# tof_board.net
KiCad netlist of a schematic drawn in Altium Designer
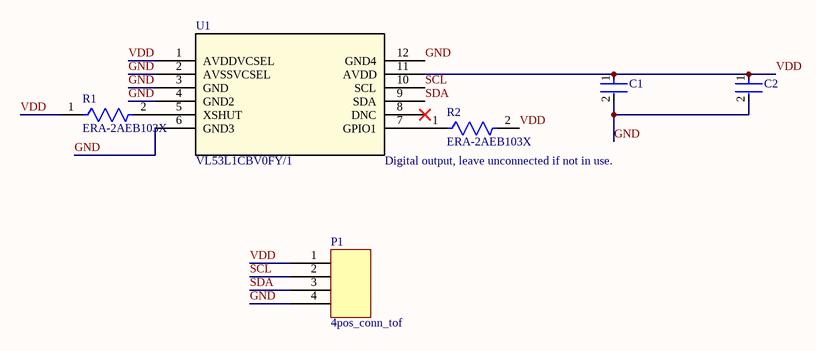
[diagram p0: tof_board.SchDoc]

(export (version "E")
  (design (tool "Eeschema 10.0.6"))
  (components
    (comp (ref "C1")
      (value "C0402C104K8PACTU")
      (footprint "FP-C0402-BB-MFG")
      (description "CAP CER 0.1UF 10V X5R 0402")
      (fields (field (name "MANUFACTURER") "Kemet") (field (name "TOLERANCE") "0.1"))
      (libsource (lib "Altium Content Vault") (part "b4654b650e69147ec39a6b967a45e02"))
    )
    (comp (ref "C2")
      (value "GRM155R60J475ME47D")
      (footprint "FP-GRM155-0_1-IPC_B")
      (description "Chip Multilayer Ceramic Capacitors for General Purpose, 0402, 4.7uF, X5R, 15%, 20%, 6.3V")
      (fields (field (name "VOLTAGE") "6.3V") (field (name "TOLERANCE") "20%"))
      (libsource (lib "Altium Content Vault") (part "11868f565c42a9108669ba33697ecf6"))
    )
    (comp (ref "P1")
      (value "4pos_conn_tof")
      (footprint "4pos_conn_tof")
      (libsource (lib "tof_board") (part "4pos_conn_tof"))
    )
    (comp (ref "R1")
      (value "ERA-2AEB103X")
      (footprint "FP-ERA2A-MFG")
      (description "RES SMD 10K OHM 0.1% 1/16W 0402")
      (fields (field (name "TOLERANCE") "0.1%") (field (name "MANUFACTURER") "Panasonic"))
      (libsource (lib "Altium Content Vault") (part "1029c3af85768c4190bb7ad29bc67b5"))
    )
    (comp (ref "R2")
      (value "ERA-2AEB103X")
      (footprint "FP-ERA2A-MFG")
      (description "RES SMD 10K OHM 0.1% 1/16W 0402")
      (fields (field (name "TOLERANCE") "0.1%") (field (name "MANUFACTURER") "Panasonic"))
      (libsource (lib "Altium Content Vault") (part "1029c3af85768c4190bb7ad29bc67b5"))
    )
    (comp (ref "U1")
      (value "VL53L1CBV0FY/1")
      (footprint "QFN_BV0FY/1_STM")
      (description "No Description Available")
      (fields (field (name "COPYRIGHT") "Copyright (C) 2022 Ultra Librarian. All rights reserved."))
      (libsource (lib "tof_board") (part "VL53L1CBV0FY/1"))
    )
  )
  (nets
    (net (code "1") (name "/GND") (class "Default")
      (node (ref "C1") (pin "2") (pinfunction "2_2") (pintype "passive"))
      (node (ref "C2") (pin "2") (pinfunction "2_2") (pintype "passive"))
      (node (ref "P1") (pin "4") (pinfunction "4_4") (pintype "passive"))
      (node (ref "U1") (pin "12") (pinfunction "GND4_12") (pintype "passive"))
      (node (ref "U1") (pin "2") (pinfunction "AVSSVCSEL_2") (pintype "passive"))
      (node (ref "U1") (pin "3") (pinfunction "GND_3") (pintype "passive"))
      (node (ref "U1") (pin "4") (pinfunction "GND2_4") (pintype "passive"))
      (node (ref "U1") (pin "6") (pinfunction "GND3_6") (pintype "passive"))
    )
    (net (code "2") (name "/SCL") (class "Default")
      (node (ref "P1") (pin "2") (pinfunction "2_2") (pintype "passive"))
      (node (ref "U1") (pin "10") (pinfunction "SCL_10") (pintype "passive"))
    )
    (net (code "3") (name "/SDA") (class "Default")
      (node (ref "P1") (pin "3") (pinfunction "3_3") (pintype "passive"))
      (node (ref "U1") (pin "9") (pinfunction "SDA_9") (pintype "passive"))
    )
    (net (code "4") (name "/VDD") (class "Default")
      (node (ref "C1") (pin "1") (pinfunction "1_1") (pintype "passive"))
      (node (ref "C2") (pin "1") (pinfunction "1_1") (pintype "passive"))
      (node (ref "P1") (pin "1") (pinfunction "1_1") (pintype "passive"))
      (node (ref "R1") (pin "1") (pinfunction "1_1") (pintype "passive"))
      (node (ref "R2") (pin "2") (pinfunction "2_2") (pintype "passive"))
      (node (ref "U1") (pin "1") (pinfunction "AVDDVCSEL_1") (pintype "power_in"))
      (node (ref "U1") (pin "11") (pinfunction "AVDD_11") (pintype "power_in"))
    )
    (net (code "5") (name "Net-(U1-GPIO1)") (class "Default")
      (node (ref "R2") (pin "1") (pinfunction "1_1") (pintype "passive"))
      (node (ref "U1") (pin "7") (pinfunction "GPIO1_7") (pintype "passive"))
    )
    (net (code "6") (name "Net-(U1-XSHUT)") (class "Default")
      (node (ref "R1") (pin "2") (pinfunction "2_2") (pintype "passive"))
      (node (ref "U1") (pin "5") (pinfunction "XSHUT_5") (pintype "passive"))
    )
    (net (code "7") (name "unconnected-(U1-DNC-Pad8)") (class "Default")
      (node (ref "U1") (pin "8") (pinfunction "DNC_8") (pintype "passive+no_connect"))
    )
  )
)
